# FAT93.net
KiCad netlist of a schematic drawn in Altium Designer
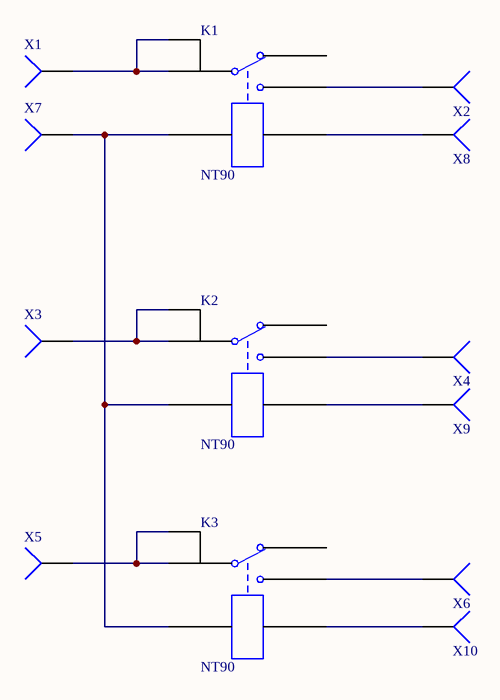
[diagram p0: FAT93.SchDoc]

(export (version "E")
  (design (tool "Eeschema 10.0.6"))
  (components
    (comp (ref "K1")
      (value "NT90")
      (footprint "NT90")
      (description "Single-Pole Dual-Throw Relay")
      (fields (field (name "MANUFACTURER") "Generic Components") (field (name "PUBLISHER") "Altium Limited"))
      (libsource (lib "PAL") (part "NT90"))
    )
    (comp (ref "K2")
      (value "NT90")
      (footprint "NT90")
      (description "Single-Pole Dual-Throw Relay")
      (fields (field (name "MANUFACTURER") "Generic Components") (field (name "PUBLISHER") "Altium Limited"))
      (libsource (lib "PAL") (part "NT90"))
    )
    (comp (ref "K3")
      (value "NT90")
      (footprint "NT90")
      (description "Single-Pole Dual-Throw Relay")
      (fields (field (name "MANUFACTURER") "Generic Components") (field (name "PUBLISHER") "Altium Limited"))
      (libsource (lib "PAL") (part "NT90"))
    )
    (comp (ref "X1")
      (value "Socket")
      (footprint "k13-4-9")
      (fields (field (name "MANUFACTURER") "Generic Components") (field (name "PUBLISHER") "Altium Limited"))
      (libsource (lib "Miscellaneous Connectors") (part "Socket"))
    )
    (comp (ref "X2")
      (value "Socket")
      (footprint "k13-4-9")
      (fields (field (name "MANUFACTURER") "Generic Components") (field (name "PUBLISHER") "Altium Limited"))
      (libsource (lib "Miscellaneous Connectors") (part "Socket"))
    )
    (comp (ref "X3")
      (value "Socket")
      (footprint "k13-4-9")
      (fields (field (name "MANUFACTURER") "Generic Components") (field (name "PUBLISHER") "Altium Limited"))
      (libsource (lib "Miscellaneous Connectors") (part "Socket"))
    )
    (comp (ref "X4")
      (value "Socket")
      (footprint "k13-4-9")
      (fields (field (name "MANUFACTURER") "Generic Components") (field (name "PUBLISHER") "Altium Limited"))
      (libsource (lib "Miscellaneous Connectors") (part "Socket"))
    )
    (comp (ref "X5")
      (value "Socket")
      (footprint "k13-4-9")
      (fields (field (name "MANUFACTURER") "Generic Components") (field (name "PUBLISHER") "Altium Limited"))
      (libsource (lib "Miscellaneous Connectors") (part "Socket"))
    )
    (comp (ref "X6")
      (value "Socket")
      (footprint "k13-4-9")
      (fields (field (name "MANUFACTURER") "Generic Components") (field (name "PUBLISHER") "Altium Limited"))
      (libsource (lib "Miscellaneous Connectors") (part "Socket"))
    )
    (comp (ref "X7")
      (value "Socket")
      (footprint "DJ614-2.8")
      (fields (field (name "MANUFACTURER") "Generic Components") (field (name "PUBLISHER") "Altium Limited"))
      (libsource (lib "Miscellaneous Connectors") (part "Socket"))
    )
    (comp (ref "X8")
      (value "Socket")
      (footprint "DJ614-2.8")
      (fields (field (name "MANUFACTURER") "Generic Components") (field (name "PUBLISHER") "Altium Limited"))
      (libsource (lib "Miscellaneous Connectors") (part "Socket"))
    )
    (comp (ref "X9")
      (value "Socket")
      (footprint "DJ614-2.8")
      (fields (field (name "MANUFACTURER") "Generic Components") (field (name "PUBLISHER") "Altium Limited"))
      (libsource (lib "Miscellaneous Connectors") (part "Socket"))
    )
    (comp (ref "X10")
      (value "Socket")
      (footprint "DJ614-2.8")
      (fields (field (name "MANUFACTURER") "Generic Components") (field (name "PUBLISHER") "Altium Limited"))
      (libsource (lib "Miscellaneous Connectors") (part "Socket"))
    )
  )
  (nets
    (net (code "1") (name "Net-(K1-Pad1)") (class "Default")
      (node (ref "K1") (pin "1") (pinfunction "1_1") (pintype "passive"))
      (node (ref "K1") (pin "6") (pinfunction "6_6") (pintype "passive"))
      (node (ref "X1") (pin "1") (pinfunction "1_1") (pintype "passive"))
    )
    (net (code "2") (name "Net-(K1-Pad3)") (class "Default")
      (node (ref "K1") (pin "3") (pinfunction "3_3") (pintype "passive"))
      (node (ref "X2") (pin "1") (pinfunction "1_1") (pintype "passive"))
    )
    (net (code "3") (name "Net-(K1-Pad4)") (class "Default")
      (node (ref "K1") (pin "4") (pinfunction "4_4") (pintype "passive"))
      (node (ref "K2") (pin "4") (pinfunction "4_4") (pintype "passive"))
      (node (ref "K3") (pin "4") (pinfunction "4_4") (pintype "passive"))
      (node (ref "X7") (pin "1") (pinfunction "1_1") (pintype "passive"))
    )
    (net (code "4") (name "Net-(K1-Pad5)") (class "Default")
      (node (ref "K1") (pin "5") (pinfunction "5_5") (pintype "passive"))
      (node (ref "X8") (pin "1") (pinfunction "1_1") (pintype "passive"))
    )
    (net (code "5") (name "Net-(K2-Pad1)") (class "Default")
      (node (ref "K2") (pin "1") (pinfunction "1_1") (pintype "passive"))
      (node (ref "K2") (pin "6") (pinfunction "6_6") (pintype "passive"))
      (node (ref "X3") (pin "1") (pinfunction "1_1") (pintype "passive"))
    )
    (net (code "6") (name "Net-(K2-Pad3)") (class "Default")
      (node (ref "K2") (pin "3") (pinfunction "3_3") (pintype "passive"))
      (node (ref "X4") (pin "1") (pinfunction "1_1") (pintype "passive"))
    )
    (net (code "7") (name "Net-(K2-Pad5)") (class "Default")
      (node (ref "K2") (pin "5") (pinfunction "5_5") (pintype "passive"))
      (node (ref "X9") (pin "1") (pinfunction "1_1") (pintype "passive"))
    )
    (net (code "8") (name "Net-(K3-Pad1)") (class "Default")
      (node (ref "K3") (pin "1") (pinfunction "1_1") (pintype "passive"))
      (node (ref "K3") (pin "6") (pinfunction "6_6") (pintype "passive"))
      (node (ref "X5") (pin "1") (pinfunction "1_1") (pintype "passive"))
    )
    (net (code "9") (name "Net-(K3-Pad3)") (class "Default")
      (node (ref "K3") (pin "3") (pinfunction "3_3") (pintype "passive"))
      (node (ref "X6") (pin "1") (pinfunction "1_1") (pintype "passive"))
    )
    (net (code "10") (name "Net-(K3-Pad5)") (class "Default")
      (node (ref "K3") (pin "5") (pinfunction "5_5") (pintype "passive"))
      (node (ref "X10") (pin "1") (pinfunction "1_1") (pintype "passive"))
    )
    (net (code "11") (name "unconnected-(K1-Pad2)") (class "Default")
      (node (ref "K1") (pin "2") (pinfunction "2_2") (pintype "passive"))
    )
    (net (code "12") (name "unconnected-(K2-Pad2)") (class "Default")
      (node (ref "K2") (pin "2") (pinfunction "2_2") (pintype "passive"))
    )
    (net (code "13") (name "unconnected-(K3-Pad2)") (class "Default")
      (node (ref "K3") (pin "2") (pinfunction "2_2") (pintype "passive"))
    )
  )
)
